# GSM_SA_Schematic.net
KiCad netlist of a schematic drawn in Altium Designer
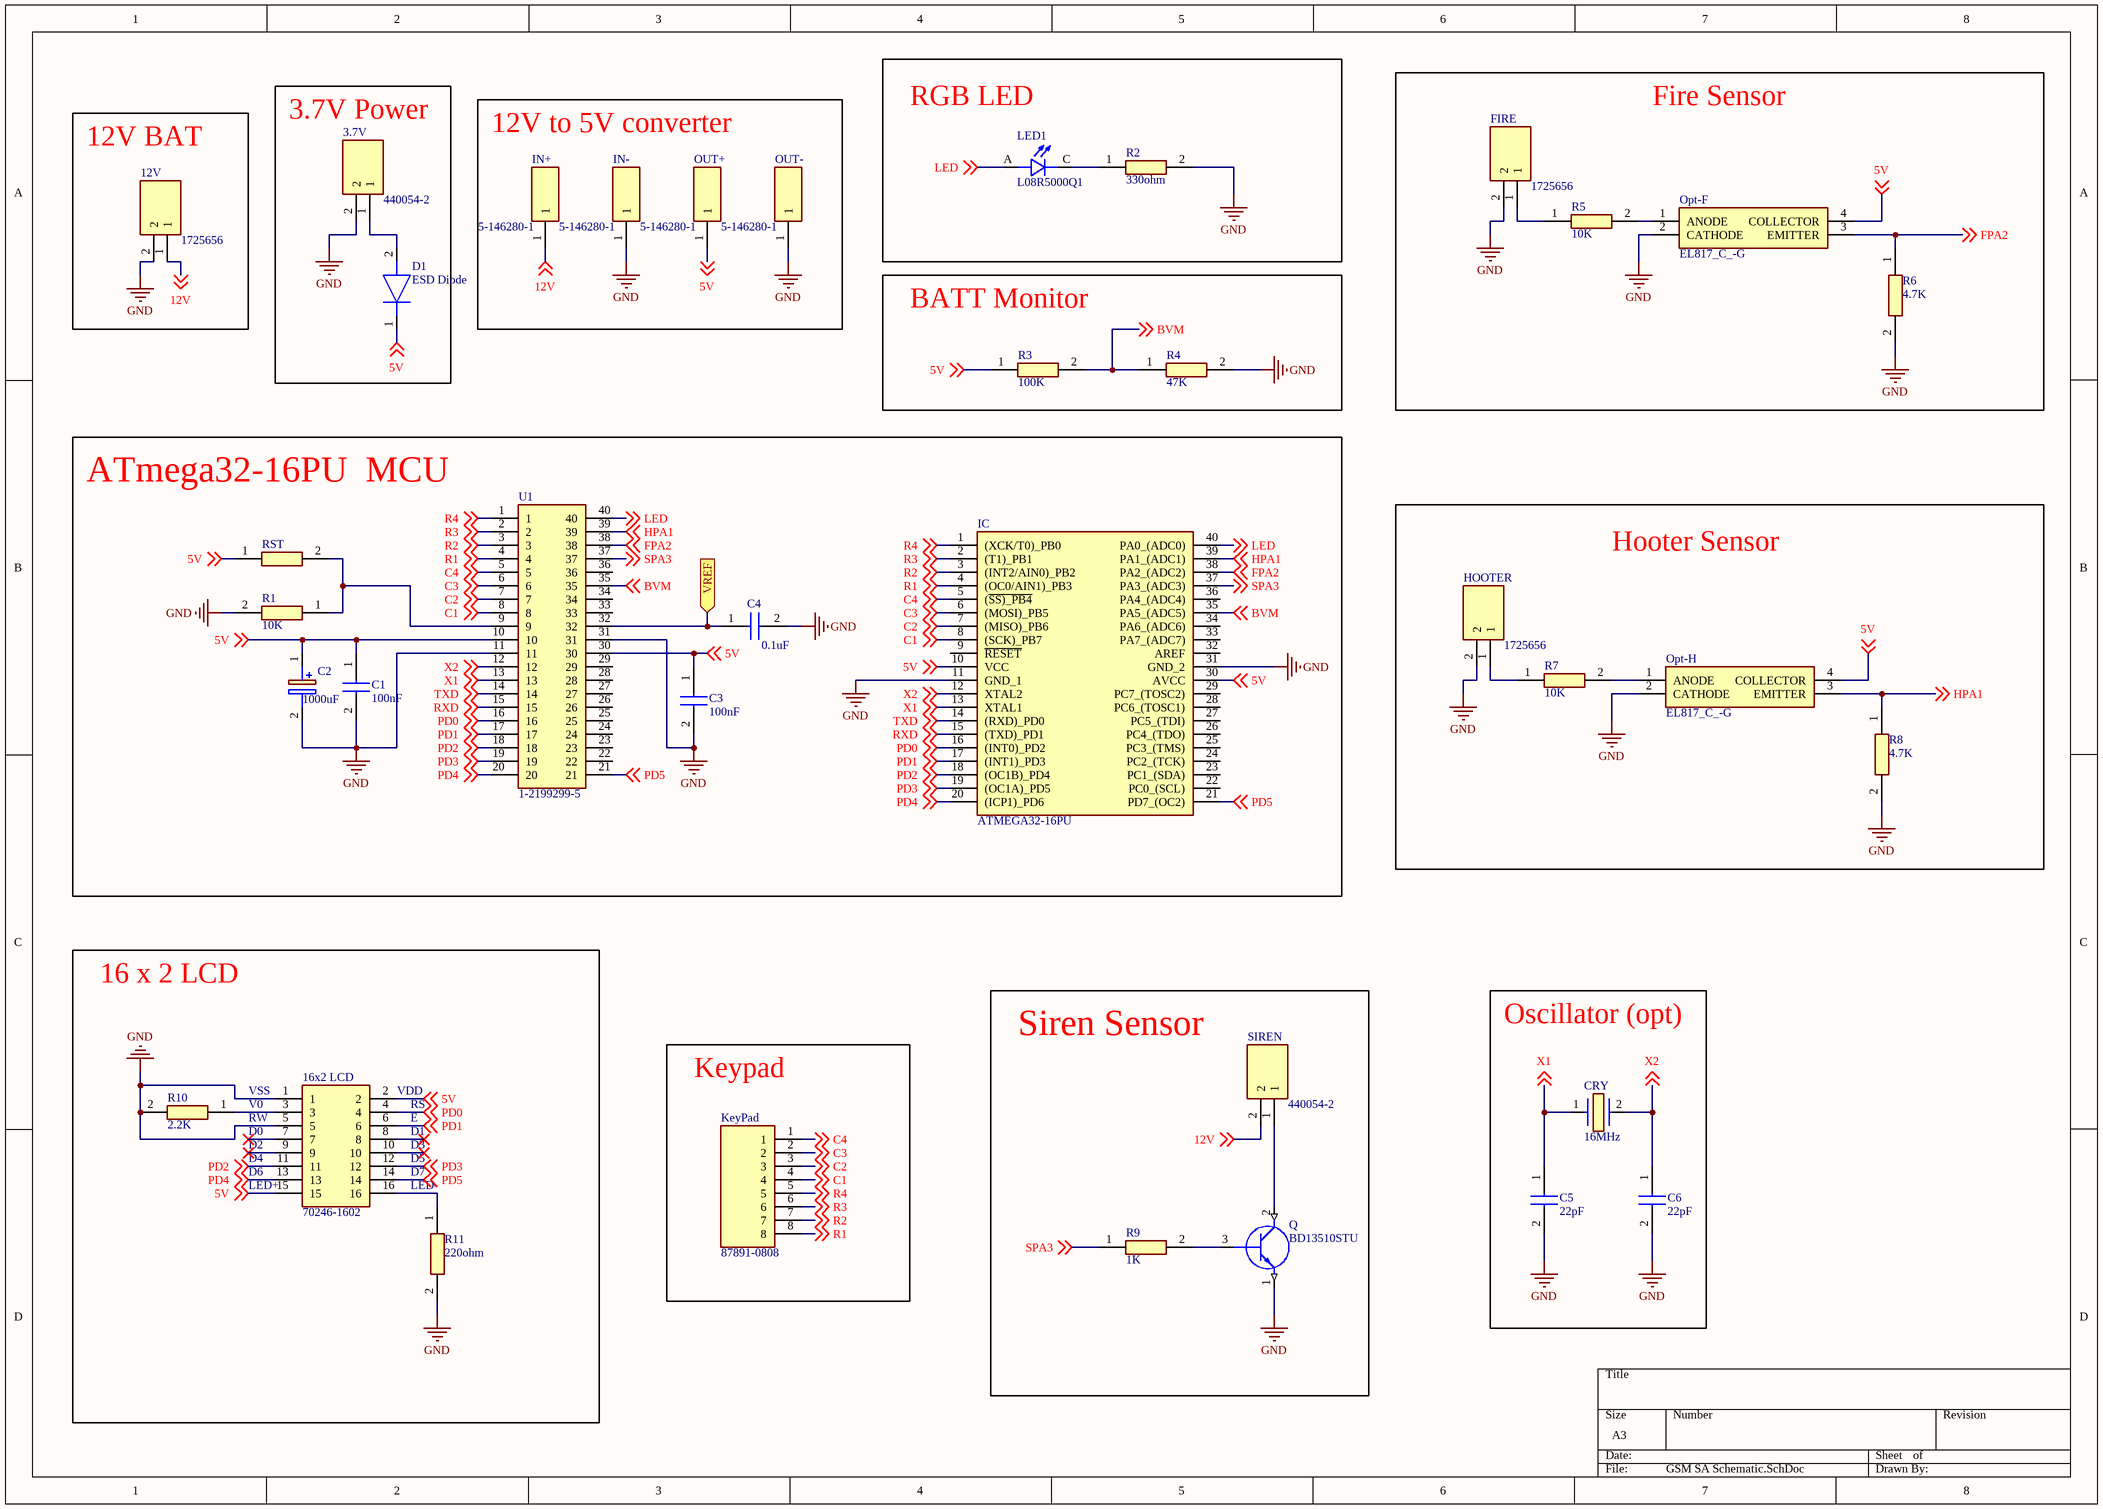
[diagram p0: GSM SA Schematic.SchDoc]

(export (version "E")
  (design (tool "Eeschema 10.0.6"))
  (components
    (comp (ref "3.7V")
      (value "440054-2")
      (footprint "SamacSys:SHDR2W70P0X200_1X2_600X470X635P")
      (description "Connector")
      (fields (field (name "MOUSER PART NUMBER") "571-440054-2"))
      (libsource (lib "SamacSys") (part "440054-2"))
    )
    (comp (ref "12V")
      (value "1725656")
      (footprint "SamacSys:1725656")
      (description "Connector")
      (fields (field (name "MOUSER PART NUMBER") "651-1725656"))
      (libsource (lib "SamacSys") (part "1725656"))
    )
    (comp (ref "16x2 LCD")
      (value "70246-1602")
      (footprint "SHDR16W99P254_2X8_2794X889X927P")
      (description "Headers & Wire Housings 2.54mm CGrid Hdr Shr d /Slt .76AuLF 16Ckt")
      (fields (field (name "MOUSER PART NUMBER") "538-70246-1602"))
      (libsource (lib "70246-1602") (part "70246-1602"))
    )
    (comp (ref "C1")
      (value "100nF")
      (footprint "SamacSys:C1206")
      (description "100nF 5% tolerance 50VDC Capacitor")
      (fields
        (field (name "MANUFACTURER_PART_NUMBER") "C1206C150F5GACTU")
        (field (name "MOUSER PART NUMBER") "80-C1206C150F5GACTU")
      )
      (libsource (lib "SamacSys") (part "C1206C150F5GACTU"))
    )
    (comp (ref "C2")
      (value "1000uF")
      (footprint "SamacSys:CAPPRD500W65D1000H1750")
      (description "1000uF 25VDC Capacitor Polarised")
      (fields
        (field (name "MANUFACTURER_PART_NUMBER") "EEU-HD1E102B")
        (field (name "MOUSER PART NUMBER") "667-EEU-HD1E102B")
      )
      (libsource (lib "SamacSys") (part "EEU-HD1E102B"))
    )
    (comp (ref "C3")
      (value "100nF")
      (footprint "SamacSys:C1206")
      (description "100nF 5% tolerance 50VDC Capacitor")
      (fields
        (field (name "MANUFACTURER_PART_NUMBER") "C1206C150F5GACTU")
        (field (name "MOUSER PART NUMBER") "80-C1206C150F5GACTU")
      )
      (libsource (lib "SamacSys") (part "C1206C150F5GACTU"))
    )
    (comp (ref "C4")
      (value "0.1uF")
      (footprint "SamacSys:C1206")
      (description "0.1uF 5% tolerance 50VDC Capacitor")
      (fields
        (field (name "MANUFACTURER_PART_NUMBER") "C1206C150F5GACTU")
        (field (name "MOUSER PART NUMBER") "80-C1206C150F5GACTU")
      )
      (libsource (lib "SamacSys") (part "C1206C150F5GACTU"))
    )
    (comp (ref "C5")
      (value "22pF")
      (footprint "SamacSys:C1206")
      (description "22pF 10% tolerance 50VDC tolerance Capacitor")
      (fields
        (field (name "MANUFACTURER_PART_NUMBER") "C1206C150F5GACTU")
        (field (name "MOUSER PART NUMBER") "80-C1206C150F5GACTU")
      )
      (libsource (lib "SamacSys") (part "C1206C150F5GACTU"))
    )
    (comp (ref "C6")
      (value "22pF")
      (footprint "SamacSys:C1206")
      (description "22pF 10% tolerance 50VDC tolerance Capacitor")
      (fields
        (field (name "MANUFACTURER_PART_NUMBER") "C1206C150F5GACTU")
        (field (name "MOUSER PART NUMBER") "80-C1206C150F5GACTU")
      )
      (libsource (lib "SamacSys") (part "C1206C150F5GACTU"))
    )
    (comp (ref "CRY")
      (value "16MHz")
      (footprint "SamacSys:ECS160185PXGMTR")
      (description "Crystal or Oscillator")
      (fields
        (field (name "MANUFACTURER_PART_NUMBER") "ECS-160-18-5PX-GM-TR")
        (field (name "MOUSER PART NUMBER") "520-160-18-5PX-GM-TR")
      )
      (libsource (lib "SamacSys") (part "ECS-160-18-5PX-GM-TR"))
    )
    (comp (ref "D1")
      (value "ESD Diode")
      (footprint "SamacSys:DIOM5336X262N")
      (description "ESD Suppressors / TVS Diodes 600W 5.0V")
      (fields
        (field (name "MANUFACTURER_PART_NUMBER") "SMBJ5.0CA-13-F")
        (field (name "MOUSER PART NUMBER") "621-SMBJ5.0CA-13-F")
      )
      (libsource (lib "SamacSys") (part "SMBJ5.0CA-13-F"))
    )
    (comp (ref "FIRE")
      (value "1725656")
      (footprint "SamacSys:1725656")
      (description "Connector")
      (fields (field (name "MOUSER PART NUMBER") "651-1725656"))
      (libsource (lib "SamacSys") (part "1725656"))
    )
    (comp (ref "HOOTER")
      (value "1725656")
      (footprint "SamacSys:1725656")
      (description "Connector")
      (fields (field (name "MOUSER PART NUMBER") "651-1725656"))
      (libsource (lib "SamacSys") (part "1725656"))
    )
    (comp (ref "IC")
      (value "ATMEGA32-16PU")
      (footprint "SamacSys:DIP1556W56P254L5232H483Q40N")
      (description "Integrated Circuit")
      (fields (field (name "MOUSER PART NUMBER") "556-ATMEGA32-16PU"))
      (libsource (lib "SamacSys") (part "ATMEGA32-16PU"))
    )
    (comp (ref "IN+")
      (value "5-146280-1")
      (footprint "HDRV1W67P0X254_1X1_213X234X821P")
      (description "AMP - TE CONNECTIVITY - 5-146280-1 - 01 MODII HDR SRST B/A LF")
      (fields (field (name "MOUSER PART NUMBER") "571-51462801"))
      (libsource (lib "5-146280-1") (part "5-146280-1"))
    )
    (comp (ref "IN-")
      (value "5-146280-1")
      (footprint "HDRV1W67P0X254_1X1_213X234X821P")
      (description "AMP - TE CONNECTIVITY - 5-146280-1 - 01 MODII HDR SRST B/A LF")
      (fields (field (name "MOUSER PART NUMBER") "571-51462801"))
      (libsource (lib "5-146280-1") (part "5-146280-1"))
    )
    (comp (ref "KeyPad")
      (value "87891-0808")
      (footprint "SamacSys:HDRV8W69P0X254_1X8_2032X251X1641P")
      (description "Connector")
      (fields (field (name "MOUSER PART NUMBER") "538-87891-0808"))
      (libsource (lib "SamacSys") (part "87891-0808"))
    )
    (comp (ref "LED1")
      (value "L08R5000Q1")
      (footprint "LEDRD254W57D500H1070")
      (fields (field (name "MF") "LED Technology"))
      (libsource (lib "L08R5000Q1") (part "L08R5000Q1"))
    )
    (comp (ref "Opt-F")
      (value "EL817_C_-G")
      (footprint "SamacSys:DIP762W60P254L458H480Q4N")
      (description "Integrated Circuit")
      (fields
        (field (name "MANUFACTURER_PART_NUMBER") "EL817(C)-G")
        (field (name "MOUSER PART NUMBER") "638-EL817C-G")
      )
      (libsource (lib "SamacSys") (part "EL817_C_-G"))
    )
    (comp (ref "Opt-H")
      (value "EL817_C_-G")
      (footprint "SamacSys:DIP762W60P254L458H480Q4N")
      (description "Integrated Circuit")
      (fields
        (field (name "MANUFACTURER_PART_NUMBER") "EL817(C)-G")
        (field (name "MOUSER PART NUMBER") "638-EL817C-G")
      )
      (libsource (lib "SamacSys") (part "EL817_C_-G"))
    )
    (comp (ref "OUT+")
      (value "5-146280-1")
      (footprint "HDRV1W67P0X254_1X1_213X234X821P")
      (description "AMP - TE CONNECTIVITY - 5-146280-1 - 01 MODII HDR SRST B/A LF")
      (fields (field (name "MOUSER PART NUMBER") "571-51462801"))
      (libsource (lib "5-146280-1") (part "5-146280-1"))
    )
    (comp (ref "OUT-")
      (value "5-146280-1")
      (footprint "HDRV1W67P0X254_1X1_213X234X821P")
      (description "AMP - TE CONNECTIVITY - 5-146280-1 - 01 MODII HDR SRST B/A LF")
      (fields (field (name "MOUSER PART NUMBER") "571-51462801"))
      (libsource (lib "5-146280-1") (part "5-146280-1"))
    )
    (comp (ref "Q")
      (value "BD13510STU")
      (footprint "SamacSys:TO229P345X800X1460-3P")
      (description "Transistor BJT NPN")
      (fields (field (name "MOUSER PART NUMBER") "512-BD13510STU"))
      (libsource (lib "SamacSys") (part "BD13510STU"))
    )
    (comp (ref "R1")
      (value "10K")
      (footprint "SamacSys:RESC3216X65N")
      (description "10K 1% tolerance Resistor")
      (fields
        (field (name "MANUFACTURER_PART_NUMBER") "TNPW12065K00BEEN")
        (field (name "MOUSER PART NUMBER") "71-TNPW12065K00BEEN")
      )
      (libsource (lib "SamacSys") (part "TNPW12065K00BEEN"))
    )
    (comp (ref "R2")
      (value "330ohm")
      (footprint "SamacSys:RESC3216X65N")
      (description "330ohm 1% Tolerance Resistor")
      (fields
        (field (name "MANUFACTURER_PART_NUMBER") "TNPW12065K00BEEN")
        (field (name "MOUSER PART NUMBER") "71-TNPW12065K00BEEN")
      )
      (libsource (lib "") (part "TNPW12065K00BEEN_1"))
    )
    (comp (ref "R3")
      (value "100K")
      (footprint "SamacSys:RESC3216X65N")
      (description "100K 1% tolerance Resistor")
      (fields
        (field (name "MANUFACTURER_PART_NUMBER") "TNPW12065K00BEEN")
        (field (name "MOUSER PART NUMBER") "71-TNPW12065K00BEEN")
      )
      (libsource (lib "") (part "TNPW12065K00BEEN_1"))
    )
    (comp (ref "R4")
      (value "47K")
      (footprint "SamacSys:RESC3216X65N")
      (description "47K 1% tolerance Resistor")
      (fields
        (field (name "MANUFACTURER_PART_NUMBER") "TNPW12065K00BEEN")
        (field (name "MOUSER PART NUMBER") "71-TNPW12065K00BEEN")
      )
      (libsource (lib "") (part "TNPW12065K00BEEN_1"))
    )
    (comp (ref "R5")
      (value "10K")
      (footprint "SamacSys:RESC3216X65N")
      (description "10K 1% tolerance Resistor")
      (fields
        (field (name "MANUFACTURER_PART_NUMBER") "TNPW12065K00BEEN")
        (field (name "MOUSER PART NUMBER") "71-TNPW12065K00BEEN")
      )
      (libsource (lib "") (part "TNPW12065K00BEEN_1"))
    )
    (comp (ref "R6")
      (value "4.7K")
      (footprint "SamacSys:RESC3216X65N")
      (description "4.7K 1% tolerance  Resistor")
      (fields
        (field (name "MANUFACTURER_PART_NUMBER") "TNPW12065K00BEEN")
        (field (name "MOUSER PART NUMBER") "71-TNPW12065K00BEEN")
      )
      (libsource (lib "") (part "TNPW12065K00BEEN_2"))
    )
    (comp (ref "R7")
      (value "10K")
      (footprint "SamacSys:RESC3216X65N")
      (description "10K 1% tolerance Resistor")
      (fields
        (field (name "MANUFACTURER_PART_NUMBER") "TNPW12065K00BEEN")
        (field (name "MOUSER PART NUMBER") "71-TNPW12065K00BEEN")
      )
      (libsource (lib "") (part "TNPW12065K00BEEN_1"))
    )
    (comp (ref "R8")
      (value "4.7K")
      (footprint "SamacSys:RESC3216X65N")
      (description "4.7K 1% tolerance Resistor")
      (fields
        (field (name "MANUFACTURER_PART_NUMBER") "TNPW12065K00BEEN")
        (field (name "MOUSER PART NUMBER") "71-TNPW12065K00BEEN")
      )
      (libsource (lib "") (part "TNPW12065K00BEEN_2"))
    )
    (comp (ref "R9")
      (value "1K")
      (footprint "SamacSys:RESC3116X65N")
      (description "1k 1% tolerance Resistor")
      (fields
        (field (name "MANUFACTURER_PART_NUMBER") "CMP1206-FX-1001ELF")
        (field (name "MOUSER PART NUMBER") "652-CMP1206-FX-1001L")
      )
      (libsource (lib "SamacSys") (part "CMP1206-FX-1001ELF"))
    )
    (comp (ref "R10")
      (value "2.2K")
      (footprint "SamacSys:RESC3216X65N")
      (description "2.2K 1% tolerance Resistor")
      (fields
        (field (name "MANUFACTURER_PART_NUMBER") "TNPW12065K00BEEN")
        (field (name "MOUSER PART NUMBER") "71-TNPW12065K00BEEN")
      )
      (libsource (lib "SamacSys") (part "TNPW12065K00BEEN"))
    )
    (comp (ref "R11")
      (value "220ohm")
      (footprint "SamacSys:RESC3216X65N")
      (description "220ohm 1% tolerance Resistor")
      (fields
        (field (name "MANUFACTURER_PART_NUMBER") "TNPW12065K00BEEN")
        (field (name "MOUSER PART NUMBER") "71-TNPW12065K00BEEN")
      )
      (libsource (lib "") (part "TNPW12065K00BEEN_2"))
    )
    (comp (ref "RST")
      (value "NP")
      (footprint "SamacSys:RESC3216X65N")
      (description "2 pin Switch")
      (fields
        (field (name "MANUFACTURER_PART_NUMBER") "TNPW12065K00BEEN")
        (field (name "MOUSER PART NUMBER") "71-TNPW12065K00BEEN")
      )
      (libsource (lib "") (part "TNPW12065K00BEEN_1"))
    )
    (comp (ref "SIREN")
      (value "440054-2")
      (footprint "SamacSys:SHDR2W70P0X200_1X2_600X470X635P")
      (description "Connector")
      (fields (field (name "MOUSER PART NUMBER") "571-440054-2"))
      (libsource (lib "SamacSys") (part "440054-2"))
    )
    (comp (ref "U1")
      (value "1-2199299-5")
      (footprint "SamacSys:DIPS1544W70P254L5080H530Q40N")
      (description "Connector")
      (fields (field (name "MOUSER PART NUMBER") "571-1-2199299-5"))
      (libsource (lib "SamacSys") (part "1-2199299-5"))
    )
  )
  (nets
    (net (code "1") (name "/VREF") (class "Default")
      (node (ref "C4") (pin "1") (pinfunction "1_1") (pintype "passive"))
      (node (ref "U1") (pin "32") (pinfunction "32_32") (pintype "passive"))
    )
    (net (code "2") (name "5V") (class "Default")
      (node (ref "16x2 LCD") (pin "15") (pinfunction "15_15") (pintype "passive"))
      (node (ref "16x2 LCD") (pin "2") (pinfunction "2_2") (pintype "passive"))
      (node (ref "C1") (pin "1") (pinfunction "1_1") (pintype "passive"))
      (node (ref "C2") (pin "1") (pinfunction "+_1") (pintype "passive"))
      (node (ref "C3") (pin "1") (pinfunction "1_1") (pintype "passive"))
      (node (ref "D1") (pin "1") (pinfunction "K_1") (pintype "passive"))
      (node (ref "IC") (pin "10") (pinfunction "VCC_10") (pintype "passive"))
      (node (ref "IC") (pin "30") (pinfunction "AVCC_30") (pintype "passive"))
      (node (ref "OUT+") (pin "1") (pinfunction "1_1") (pintype "passive"))
      (node (ref "Opt-F") (pin "4") (pinfunction "COLLECTOR_4") (pintype "passive"))
      (node (ref "Opt-H") (pin "4") (pinfunction "COLLECTOR_4") (pintype "passive"))
      (node (ref "R3") (pin "1") (pinfunction "1_1") (pintype "passive"))
      (node (ref "RST") (pin "1") (pinfunction "1_1") (pintype "passive"))
      (node (ref "U1") (pin "10") (pinfunction "10_10") (pintype "passive"))
      (node (ref "U1") (pin "30") (pinfunction "30_30") (pintype "passive"))
    )
    (net (code "3") (name "12V") (class "Default")
      (node (ref "12V") (pin "1") (pinfunction "1_1") (pintype "passive"))
      (node (ref "IN+") (pin "1") (pinfunction "1_1") (pintype "passive"))
      (node (ref "SIREN") (pin "2") (pinfunction "2_2") (pintype "passive"))
    )
    (net (code "4") (name "BVM") (class "Default")
      (node (ref "IC") (pin "35") (pinfunction "PA5_(ADC5)_35") (pintype "passive"))
      (node (ref "R3") (pin "2") (pinfunction "2_2") (pintype "passive"))
      (node (ref "R4") (pin "1") (pinfunction "1_1") (pintype "passive"))
      (node (ref "U1") (pin "35") (pinfunction "35_35") (pintype "passive"))
    )
    (net (code "5") (name "C1") (class "Default")
      (node (ref "IC") (pin "8") (pinfunction "(SCK)_PB7_8") (pintype "passive"))
      (node (ref "KeyPad") (pin "4") (pinfunction "4_4") (pintype "passive"))
      (node (ref "U1") (pin "8") (pinfunction "8_8") (pintype "passive"))
    )
    (net (code "6") (name "C2") (class "Default")
      (node (ref "IC") (pin "7") (pinfunction "(MISO)_PB6_7") (pintype "passive"))
      (node (ref "KeyPad") (pin "3") (pinfunction "3_3") (pintype "passive"))
      (node (ref "U1") (pin "7") (pinfunction "7_7") (pintype "passive"))
    )
    (net (code "7") (name "C3") (class "Default")
      (node (ref "IC") (pin "6") (pinfunction "(MOSI)_PB5_6") (pintype "passive"))
      (node (ref "KeyPad") (pin "2") (pinfunction "2_2") (pintype "passive"))
      (node (ref "U1") (pin "6") (pinfunction "6_6") (pintype "passive"))
    )
    (net (code "8") (name "C4") (class "Default")
      (node (ref "IC") (pin "5") (pinfunction "(~{SS)_PB4}_5") (pintype "passive"))
      (node (ref "KeyPad") (pin "1") (pinfunction "1_1") (pintype "passive"))
      (node (ref "U1") (pin "5") (pinfunction "5_5") (pintype "passive"))
    )
    (net (code "9") (name "FPA2") (class "Default")
      (node (ref "IC") (pin "38") (pinfunction "PA2_(ADC2)_38") (pintype "passive"))
      (node (ref "Opt-F") (pin "3") (pinfunction "EMITTER_3") (pintype "passive"))
      (node (ref "R6") (pin "1") (pinfunction "1_1") (pintype "passive"))
      (node (ref "U1") (pin "38") (pinfunction "38_38") (pintype "passive"))
    )
    (net (code "10") (name "GND") (class "Default")
      (node (ref "12V") (pin "2") (pinfunction "2_2") (pintype "passive"))
      (node (ref "16x2 LCD") (pin "1") (pinfunction "1_1") (pintype "passive"))
      (node (ref "16x2 LCD") (pin "5") (pinfunction "5_5") (pintype "passive"))
      (node (ref "3.7V") (pin "2") (pinfunction "2_2") (pintype "passive"))
      (node (ref "C1") (pin "2") (pinfunction "2_2") (pintype "passive"))
      (node (ref "C2") (pin "2") (pinfunction "-_2") (pintype "passive"))
      (node (ref "C3") (pin "2") (pinfunction "2_2") (pintype "passive"))
      (node (ref "C4") (pin "2") (pinfunction "2_2") (pintype "passive"))
      (node (ref "C5") (pin "2") (pinfunction "2_2") (pintype "passive"))
      (node (ref "C6") (pin "2") (pinfunction "2_2") (pintype "passive"))
      (node (ref "FIRE") (pin "2") (pinfunction "2_2") (pintype "passive"))
      (node (ref "HOOTER") (pin "2") (pinfunction "2_2") (pintype "passive"))
      (node (ref "IC") (pin "11") (pinfunction "GND_1_11") (pintype "passive"))
      (node (ref "IC") (pin "31") (pinfunction "GND_2_31") (pintype "passive"))
      (node (ref "IN-") (pin "1") (pinfunction "1_1") (pintype "passive"))
      (node (ref "OUT-") (pin "1") (pinfunction "1_1") (pintype "passive"))
      (node (ref "Opt-F") (pin "2") (pinfunction "CATHODE_2") (pintype "passive"))
      (node (ref "Opt-H") (pin "2") (pinfunction "CATHODE_2") (pintype "passive"))
      (node (ref "Q") (pin "1") (pinfunction "E_1") (pintype "output"))
      (node (ref "R1") (pin "2") (pinfunction "2_2") (pintype "passive"))
      (node (ref "R10") (pin "2") (pinfunction "2_2") (pintype "passive"))
      (node (ref "R11") (pin "2") (pinfunction "2_2") (pintype "passive"))
      (node (ref "R2") (pin "2") (pinfunction "2_2") (pintype "passive"))
      (node (ref "R4") (pin "2") (pinfunction "2_2") (pintype "passive"))
      (node (ref "R6") (pin "2") (pinfunction "2_2") (pintype "passive"))
      (node (ref "R8") (pin "2") (pinfunction "2_2") (pintype "passive"))
      (node (ref "U1") (pin "11") (pinfunction "11_11") (pintype "passive"))
      (node (ref "U1") (pin "31") (pinfunction "31_31") (pintype "passive"))
    )
    (net (code "11") (name "HPA1") (class "Default")
      (node (ref "IC") (pin "39") (pinfunction "PA1_(ADC1)_39") (pintype "passive"))
      (node (ref "Opt-H") (pin "3") (pinfunction "EMITTER_3") (pintype "passive"))
      (node (ref "R8") (pin "1") (pinfunction "1_1") (pintype "passive"))
      (node (ref "U1") (pin "39") (pinfunction "39_39") (pintype "passive"))
    )
    (net (code "12") (name "LED") (class "Default")
      (node (ref "IC") (pin "40") (pinfunction "PA0_(ADC0)_40") (pintype "passive"))
      (node (ref "LED1") (pin "A") (pinfunction "A_A") (pintype "passive"))
      (node (ref "U1") (pin "40") (pinfunction "40_40") (pintype "passive"))
    )
    (net (code "13") (name "Net-(16x2 LCD-Pad3)") (class "Default")
      (node (ref "16x2 LCD") (pin "3") (pinfunction "3_3") (pintype "passive"))
      (node (ref "R10") (pin "1") (pinfunction "1_1") (pintype "passive"))
    )
    (net (code "14") (name "Net-(16x2 LCD-Pad16)") (class "Default")
      (node (ref "16x2 LCD") (pin "16") (pinfunction "16_16") (pintype "passive"))
      (node (ref "R11") (pin "1") (pinfunction "1_1") (pintype "passive"))
    )
    (net (code "15") (name "Net-(D1-A)") (class "Default")
      (node (ref "3.7V") (pin "1") (pinfunction "1_1") (pintype "passive"))
      (node (ref "D1") (pin "2") (pinfunction "A_2") (pintype "passive"))
    )
    (net (code "16") (name "Net-(FIRE-Pad1)") (class "Default")
      (node (ref "FIRE") (pin "1") (pinfunction "1_1") (pintype "passive"))
      (node (ref "R5") (pin "1") (pinfunction "1_1") (pintype "passive"))
    )
    (net (code "17") (name "Net-(HOOTER-Pad1)") (class "Default")
      (node (ref "HOOTER") (pin "1") (pinfunction "1_1") (pintype "passive"))
      (node (ref "R7") (pin "1") (pinfunction "1_1") (pintype "passive"))
    )
    (net (code "18") (name "Net-(LED1-PadC)") (class "Default")
      (node (ref "LED1") (pin "C") (pinfunction "C_C") (pintype "passive"))
      (node (ref "R2") (pin "1") (pinfunction "1_1") (pintype "passive"))
    )
    (net (code "19") (name "Net-(Opt-F-ANODE)") (class "Default")
      (node (ref "Opt-F") (pin "1") (pinfunction "ANODE_1") (pintype "passive"))
      (node (ref "R5") (pin "2") (pinfunction "2_2") (pintype "passive"))
    )
    (net (code "20") (name "Net-(Opt-H-ANODE)") (class "Default")
      (node (ref "Opt-H") (pin "1") (pinfunction "ANODE_1") (pintype "passive"))
      (node (ref "R7") (pin "2") (pinfunction "2_2") (pintype "passive"))
    )
    (net (code "21") (name "Net-(Q-B)") (class "Default")
      (node (ref "Q") (pin "3") (pinfunction "B_3") (pintype "passive"))
      (node (ref "R9") (pin "2") (pinfunction "2_2") (pintype "passive"))
    )
    (net (code "22") (name "Net-(Q-C)") (class "Default")
      (node (ref "Q") (pin "2") (pinfunction "C_2") (pintype "input"))
      (node (ref "SIREN") (pin "1") (pinfunction "1_1") (pintype "passive"))
    )
    (net (code "23") (name "Net-(R1-Pad1)") (class "Default")
      (node (ref "R1") (pin "1") (pinfunction "1_1") (pintype "passive"))
      (node (ref "RST") (pin "2") (pinfunction "2_2") (pintype "passive"))
      (node (ref "U1") (pin "9") (pinfunction "9_9") (pintype "passive"))
    )
    (net (code "24") (name "PD0") (class "Default")
      (node (ref "16x2 LCD") (pin "4") (pinfunction "4_4") (pintype "passive"))
      (node (ref "IC") (pin "16") (pinfunction "(INT0)_PD2_16") (pintype "passive"))
      (node (ref "U1") (pin "16") (pinfunction "16_16") (pintype "passive"))
    )
    (net (code "25") (name "PD1") (class "Default")
      (node (ref "16x2 LCD") (pin "6") (pinfunction "6_6") (pintype "passive"))
      (node (ref "IC") (pin "17") (pinfunction "(INT1)_PD3_17") (pintype "passive"))
      (node (ref "U1") (pin "17") (pinfunction "17_17") (pintype "passive"))
    )
    (net (code "26") (name "PD2") (class "Default")
      (node (ref "16x2 LCD") (pin "11") (pinfunction "11_11") (pintype "passive"))
      (node (ref "IC") (pin "18") (pinfunction "(OC1B)_PD4_18") (pintype "passive"))
      (node (ref "U1") (pin "18") (pinfunction "18_18") (pintype "passive"))
    )
    (net (code "27") (name "PD3") (class "Default")
      (node (ref "16x2 LCD") (pin "12") (pinfunction "12_12") (pintype "passive"))
      (node (ref "IC") (pin "19") (pinfunction "(OC1A)_PD5_19") (pintype "passive"))
      (node (ref "U1") (pin "19") (pinfunction "19_19") (pintype "passive"))
    )
    (net (code "28") (name "PD4") (class "Default")
      (node (ref "16x2 LCD") (pin "13") (pinfunction "13_13") (pintype "passive"))
      (node (ref "IC") (pin "20") (pinfunction "(ICP1)_PD6_20") (pintype "passive"))
      (node (ref "U1") (pin "20") (pinfunction "20_20") (pintype "passive"))
    )
    (net (code "29") (name "PD5") (class "Default")
      (node (ref "16x2 LCD") (pin "14") (pinfunction "14_14") (pintype "passive"))
      (node (ref "IC") (pin "21") (pinfunction "PD7_(OC2)_21") (pintype "passive"))
      (node (ref "U1") (pin "21") (pinfunction "21_21") (pintype "passive"))
    )
    (net (code "30") (name "R1") (class "Default")
      (node (ref "IC") (pin "4") (pinfunction "(OC0/AIN1)_PB3_4") (pintype "passive"))
      (node (ref "KeyPad") (pin "8") (pinfunction "8_8") (pintype "passive"))
      (node (ref "U1") (pin "4") (pinfunction "4_4") (pintype "passive"))
    )
    (net (code "31") (name "R2") (class "Default")
      (node (ref "IC") (pin "3") (pinfunction "(INT2/AIN0)_PB2_3") (pintype "passive"))
      (node (ref "KeyPad") (pin "7") (pinfunction "7_7") (pintype "passive"))
      (node (ref "U1") (pin "3") (pinfunction "3_3") (pintype "passive"))
    )
    (net (code "32") (name "R3") (class "Default")
      (node (ref "IC") (pin "2") (pinfunction "(T1)_PB1_2") (pintype "passive"))
      (node (ref "KeyPad") (pin "6") (pinfunction "6_6") (pintype "passive"))
      (node (ref "U1") (pin "2") (pinfunction "2_2") (pintype "passive"))
    )
    (net (code "33") (name "R4") (class "Default")
      (node (ref "IC") (pin "1") (pinfunction "(XCK/T0)_PB0_1") (pintype "passive"))
      (node (ref "KeyPad") (pin "5") (pinfunction "5_5") (pintype "passive"))
      (node (ref "U1") (pin "1") (pinfunction "1_1") (pintype "passive"))
    )
    (net (code "34") (name "RXD") (class "Default")
      (node (ref "IC") (pin "15") (pinfunction "(TXD)_PD1_15") (pintype "passive"))
      (node (ref "U1") (pin "15") (pinfunction "15_15") (pintype "passive"))
    )
    (net (code "35") (name "SPA3") (class "Default")
      (node (ref "IC") (pin "37") (pinfunction "PA3_(ADC3)_37") (pintype "passive"))
      (node (ref "R9") (pin "1") (pinfunction "1_1") (pintype "passive"))
      (node (ref "U1") (pin "37") (pinfunction "37_37") (pintype "passive"))
    )
    (net (code "36") (name "TXD") (class "Default")
      (node (ref "IC") (pin "14") (pinfunction "(RXD)_PD0_14") (pintype "passive"))
      (node (ref "U1") (pin "14") (pinfunction "14_14") (pintype "passive"))
    )
    (net (code "37") (name "X1") (class "Default")
      (node (ref "C5") (pin "1") (pinfunction "1_1") (pintype "passive"))
      (node (ref "CRY") (pin "1") (pinfunction "1_1") (pintype "passive"))
      (node (ref "IC") (pin "13") (pinfunction "XTAL1_13") (pintype "passive"))
      (node (ref "U1") (pin "13") (pinfunction "13_13") (pintype "passive"))
    )
    (net (code "38") (name "X2") (class "Default")
      (node (ref "C6") (pin "1") (pinfunction "1_1") (pintype "passive"))
      (node (ref "CRY") (pin "2") (pinfunction "2_2") (pintype "passive"))
      (node (ref "IC") (pin "12") (pinfunction "XTAL2_12") (pintype "passive"))
      (node (ref "U1") (pin "12") (pinfunction "12_12") (pintype "passive"))
    )
    (net (code "39") (name "unconnected-(16x2 LCD-Pad7)") (class "Default")
      (node (ref "16x2 LCD") (pin "7") (pinfunction "7_7") (pintype "passive+no_connect"))
    )
    (net (code "40") (name "unconnected-(16x2 LCD-Pad8)") (class "Default")
      (node (ref "16x2 LCD") (pin "8") (pinfunction "8_8") (pintype "passive+no_connect"))
    )
    (net (code "41") (name "unconnected-(16x2 LCD-Pad9)") (class "Default")
      (node (ref "16x2 LCD") (pin "9") (pinfunction "9_9") (pintype "passive+no_connect"))
    )
    (net (code "42") (name "unconnected-(16x2 LCD-Pad10)") (class "Default")
      (node (ref "16x2 LCD") (pin "10") (pinfunction "10_10") (pintype "passive+no_connect"))
    )
    (net (code "43") (name "unconnected-(IC-AREF-Pad32)") (class "Default")
      (node (ref "IC") (pin "32") (pinfunction "AREF_32") (pintype "passive"))
    )
    (net (code "44") (name "unconnected-(IC-PA4_(ADC4)-Pad36)") (class "Default")
      (node (ref "IC") (pin "36") (pinfunction "PA4_(ADC4)_36") (pintype "passive"))
    )
    (net (code "45") (name "unconnected-(IC-PA6_(ADC6)-Pad34)") (class "Default")
      (node (ref "IC") (pin "34") (pinfunction "PA6_(ADC6)_34") (pintype "passive"))
    )
    (net (code "46") (name "unconnected-(IC-PA7_(ADC7)-Pad33)") (class "Default")
      (node (ref "IC") (pin "33") (pinfunction "PA7_(ADC7)_33") (pintype "passive"))
    )
    (net (code "47") (name "unconnected-(IC-PC0_(SCL)-Pad22)") (class "Default")
      (node (ref "IC") (pin "22") (pinfunction "PC0_(SCL)_22") (pintype "passive"))
    )
    (net (code "48") (name "unconnected-(IC-PC1_(SDA)-Pad23)") (class "Default")
      (node (ref "IC") (pin "23") (pinfunction "PC1_(SDA)_23") (pintype "passive"))
    )
    (net (code "49") (name "unconnected-(IC-PC2_(TCK)-Pad24)") (class "Default")
      (node (ref "IC") (pin "24") (pinfunction "PC2_(TCK)_24") (pintype "passive"))
    )
    (net (code "50") (name "unconnected-(IC-PC3_(TMS)-Pad25)") (class "Default")
      (node (ref "IC") (pin "25") (pinfunction "PC3_(TMS)_25") (pintype "passive"))
    )
    (net (code "51") (name "unconnected-(IC-PC4_(TDO)-Pad26)") (class "Default")
      (node (ref "IC") (pin "26") (pinfunction "PC4_(TDO)_26") (pintype "passive"))
    )
    (net (code "52") (name "unconnected-(IC-PC5_(TDI)-Pad27)") (class "Default")
      (node (ref "IC") (pin "27") (pinfunction "PC5_(TDI)_27") (pintype "passive"))
    )
    (net (code "53") (name "unconnected-(IC-PC6_(TOSC1)-Pad28)") (class "Default")
      (node (ref "IC") (pin "28") (pinfunction "PC6_(TOSC1)_28") (pintype "passive"))
    )
    (net (code "54") (name "unconnected-(IC-PC7_(TOSC2)-Pad29)") (class "Default")
      (node (ref "IC") (pin "29") (pinfunction "PC7_(TOSC2)_29") (pintype "passive"))
    )
    (net (code "55") (name "unconnected-(IC-~{RESET}-Pad9)") (class "Default")
      (node (ref "IC") (pin "9") (pinfunction "~{RESET}_9") (pintype "passive"))
    )
    (net (code "56") (name "unconnected-(U1-Pad22)") (class "Default")
      (node (ref "U1") (pin "22") (pinfunction "22_22") (pintype "passive"))
    )
    (net (code "57") (name "unconnected-(U1-Pad23)") (class "Default")
      (node (ref "U1") (pin "23") (pinfunction "23_23") (pintype "passive"))
    )
    (net (code "58") (name "unconnected-(U1-Pad24)") (class "Default")
      (node (ref "U1") (pin "24") (pinfunction "24_24") (pintype "passive"))
    )
    (net (code "59") (name "unconnected-(U1-Pad25)") (class "Default")
      (node (ref "U1") (pin "25") (pinfunction "25_25") (pintype "passive"))
    )
    (net (code "60") (name "unconnected-(U1-Pad26)") (class "Default")
      (node (ref "U1") (pin "26") (pinfunction "26_26") (pintype "passive"))
    )
    (net (code "61") (name "unconnected-(U1-Pad27)") (class "Default")
      (node (ref "U1") (pin "27") (pinfunction "27_27") (pintype "passive"))
    )
    (net (code "62") (name "unconnected-(U1-Pad28)") (class "Default")
      (node (ref "U1") (pin "28") (pinfunction "28_28") (pintype "passive"))
    )
    (net (code "63") (name "unconnected-(U1-Pad29)") (class "Default")
      (node (ref "U1") (pin "29") (pinfunction "29_29") (pintype "passive"))
    )
    (net (code "64") (name "unconnected-(U1-Pad33)") (class "Default")
      (node (ref "U1") (pin "33") (pinfunction "33_33") (pintype "passive"))
    )
    (net (code "65") (name "unconnected-(U1-Pad34)") (class "Default")
      (node (ref "U1") (pin "34") (pinfunction "34_34") (pintype "passive"))
    )
    (net (code "66") (name "unconnected-(U1-Pad36)") (class "Default")
      (node (ref "U1") (pin "36") (pinfunction "36_36") (pintype "passive"))
    )
  )
)
